# ETHERNET.net
KiCad netlist of a schematic drawn in Altium Designer
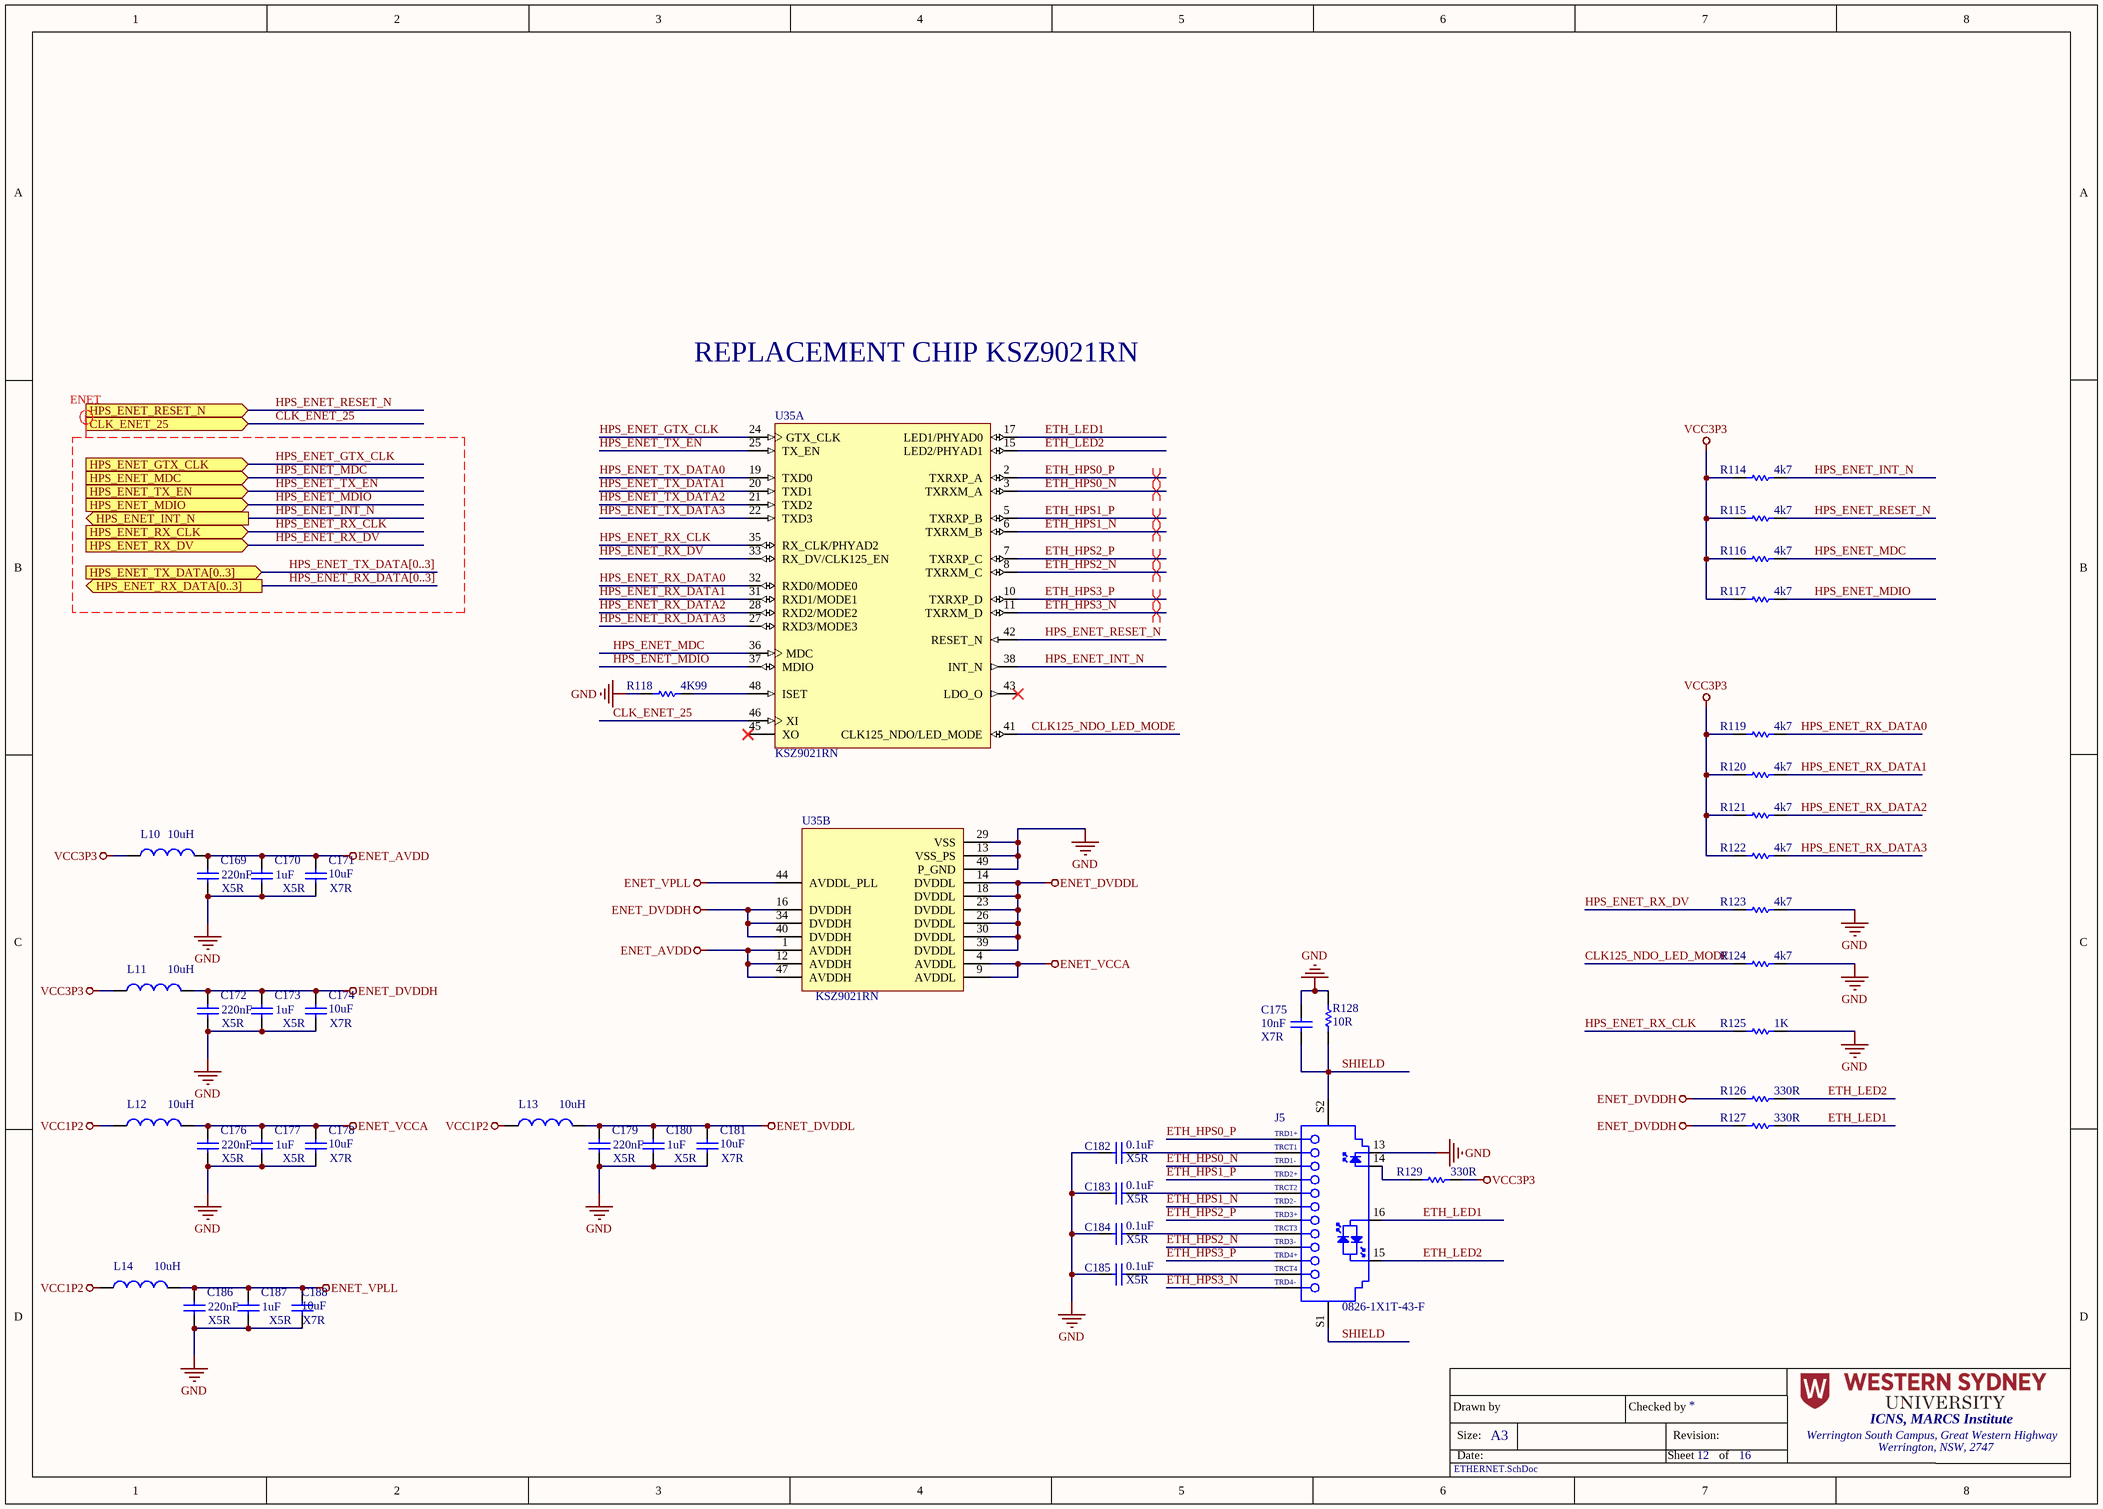
[diagram p0: ETHERNET.SchDoc]

(export (version "E")
  (design (tool "Eeschema 10.0.6"))
  (components
    (comp (ref "C169")
      (value "220nF")
      (footprint "CAP 0201 (0603)")
      (description "Cap Multilayer Ceramic 220nF 10V X5R 0201 ±10% Tolerance")
      (fields
        (field (name "TOLERANCE") "10%")
        (field (name "DIELECTRIC") "X5R")
        (field (name "MANUFACTURER PART NUMBER") "GRM033R61A224KE90D")
        (field (name "SOURCE") "ICNS_PropheseeLib.SchLib")
      )
      (libsource (lib "Western Sydney University - ICNS") (part "Symbol"))
    )
    (comp (ref "C170")
      (value "1uF")
      (footprint "CAP 0201 (0603)")
      (description "Cap Ceramic 1uF 10V X5R 10% Pad SMD 0201 85C T/R")
      (fields
        (field (name "TOLERANCE") "10%")
        (field (name "DIELECTRIC") "X5R")
        (field (name "MANUFACTURER") "Samsung")
        (field (name "SOURCE") "ICNS_PropheseeLib.SchLib")
      )
      (libsource (lib "Western Sydney University - ICNS") (part "Symbol"))
    )
    (comp (ref "C171")
      (value "10uF")
      (footprint "CAP 0805 (2012)")
      (description "0805 10 uF 10 V ±10 % Tolerance X7R Surface Mount Multilayer Ceramic Capacitor")
      (fields
        (field (name "TOLERANCE") "10%")
        (field (name "DIELECTRIC") "X7R")
        (field (name "MANUFACTURER PART NUMBER") "GCM21BR71A106KE22K")
        (field (name "SOURCE") "ICNS_PropheseeLib.SchLib")
      )
      (libsource (lib "Western Sydney University - ICNS") (part "GCM21BR71A106KE22K"))
    )
    (comp (ref "C172")
      (value "220nF")
      (footprint "CAP 0201 (0603)")
      (description "Cap Multilayer Ceramic 220nF 10V X5R 0201 ±10% Tolerance")
      (fields
        (field (name "TOLERANCE") "10%")
        (field (name "DIELECTRIC") "X5R")
        (field (name "MANUFACTURER PART NUMBER") "GRM033R61A224KE90D")
        (field (name "SOURCE") "ICNS_PropheseeLib.SchLib")
      )
      (libsource (lib "Western Sydney University - ICNS") (part "Symbol"))
    )
    (comp (ref "C173")
      (value "1uF")
      (footprint "CAP 0201 (0603)")
      (description "Cap Ceramic 1uF 10V X5R 10% Pad SMD 0201 85C T/R")
      (fields
        (field (name "TOLERANCE") "10%")
        (field (name "DIELECTRIC") "X5R")
        (field (name "MANUFACTURER") "Samsung")
        (field (name "SOURCE") "ICNS_PropheseeLib.SchLib")
      )
      (libsource (lib "Western Sydney University - ICNS") (part "Symbol"))
    )
    (comp (ref "C174")
      (value "10uF")
      (footprint "CAP 0805 (2012)")
      (description "0805 10 uF 10 V ±10 % Tolerance X7R Surface Mount Multilayer Ceramic Capacitor")
      (fields
        (field (name "TOLERANCE") "10%")
        (field (name "DIELECTRIC") "X7R")
        (field (name "MANUFACTURER PART NUMBER") "GCM21BR71A106KE22K")
        (field (name "SOURCE") "ICNS_PropheseeLib.SchLib")
      )
      (libsource (lib "Western Sydney University - ICNS") (part "GCM21BR71A106KE22K"))
    )
    (comp (ref "C175")
      (value "10nF")
      (footprint "CAP 0201 (0603)")
      (description "Cap Multilayer Ceramic 10nF 10V X7R 0201 ±10 % Tolerance SMT")
      (fields
        (field (name "TOLERANCE") "10%")
        (field (name "VOLTAGE") "10V")
        (field (name "DIELECTRIC") "X7R")
        (field (name "SOURCE") "ICNS_PropheseeLib.SchLib")
      )
      (libsource (lib "") (part "Symbol_3"))
    )
    (comp (ref "C176")
      (value "220nF")
      (footprint "CAP 0201 (0603)")
      (description "Cap Multilayer Ceramic 220nF 10V X5R 0201 ±10% Tolerance")
      (fields
        (field (name "TOLERANCE") "10%")
        (field (name "DIELECTRIC") "X5R")
        (field (name "MANUFACTURER PART NUMBER") "GRM033R61A224KE90D")
        (field (name "SOURCE") "ICNS_PropheseeLib.SchLib")
      )
      (libsource (lib "Western Sydney University - ICNS") (part "Symbol"))
    )
    (comp (ref "C177")
      (value "1uF")
      (footprint "CAP 0201 (0603)")
      (description "Cap Ceramic 1uF 10V X5R 10% Pad SMD 0201 85C T/R")
      (fields
        (field (name "TOLERANCE") "10%")
        (field (name "DIELECTRIC") "X5R")
        (field (name "MANUFACTURER") "Samsung")
        (field (name "SOURCE") "ICNS_PropheseeLib.SchLib")
      )
      (libsource (lib "Western Sydney University - ICNS") (part "Symbol"))
    )
    (comp (ref "C178")
      (value "10uF")
      (footprint "CAP 0805 (2012)")
      (description "0805 10 uF 10 V ±10 % Tolerance X7R Surface Mount Multilayer Ceramic Capacitor")
      (fields
        (field (name "TOLERANCE") "10%")
        (field (name "DIELECTRIC") "X7R")
        (field (name "MANUFACTURER PART NUMBER") "GCM21BR71A106KE22K")
        (field (name "SOURCE") "ICNS_PropheseeLib.SchLib")
      )
      (libsource (lib "Western Sydney University - ICNS") (part "GCM21BR71A106KE22K"))
    )
    (comp (ref "C179")
      (value "220nF")
      (footprint "CAP 0201 (0603)")
      (description "Cap Multilayer Ceramic 220nF 10V X5R 0201 ±10% Tolerance")
      (fields
        (field (name "TOLERANCE") "10%")
        (field (name "DIELECTRIC") "X5R")
        (field (name "MANUFACTURER PART NUMBER") "GRM033R61A224KE90D")
        (field (name "SOURCE") "ICNS_PropheseeLib.SchLib")
      )
      (libsource (lib "Western Sydney University - ICNS") (part "Symbol"))
    )
    (comp (ref "C180")
      (value "1uF")
      (footprint "CAP 0201 (0603)")
      (description "Cap Ceramic 1uF 10V X5R 10% Pad SMD 0201 85C T/R")
      (fields
        (field (name "TOLERANCE") "10%")
        (field (name "DIELECTRIC") "X5R")
        (field (name "MANUFACTURER") "Samsung")
        (field (name "SOURCE") "ICNS_PropheseeLib.SchLib")
      )
      (libsource (lib "Western Sydney University - ICNS") (part "Symbol"))
    )
    (comp (ref "C181")
      (value "10uF")
      (footprint "CAP 0805 (2012)")
      (description "0805 10 uF 10 V ±10 % Tolerance X7R Surface Mount Multilayer Ceramic Capacitor")
      (fields
        (field (name "TOLERANCE") "10%")
        (field (name "DIELECTRIC") "X7R")
        (field (name "MANUFACTURER PART NUMBER") "GCM21BR71A106KE22K")
        (field (name "SOURCE") "ICNS_PropheseeLib.SchLib")
      )
      (libsource (lib "Western Sydney University - ICNS") (part "GCM21BR71A106KE22K"))
    )
    (comp (ref "C182")
      (value "0.1uF")
      (footprint "CAP 0201 (0603)")
      (description "Cap Ceramic 0.1uF 10V X5R 10% Pad SMD 0201 85C T/R")
      (fields
        (field (name "TOLERANCE") "10%")
        (field (name "DIELECTRIC") "X5R")
        (field (name "MANUFACTURER PART NUMBER") "CL03A104KP3NNNC")
        (field (name "SOURCE") "ICNS_PropheseeLib.SchLib")
      )
      (libsource (lib "Western Sydney University - ICNS") (part "CL03A104KP3NNNC"))
    )
    (comp (ref "C183")
      (value "0.1uF")
      (footprint "CAP 0201 (0603)")
      (description "Cap Ceramic 0.1uF 10V X5R 10% Pad SMD 0201 85C T/R")
      (fields
        (field (name "TOLERANCE") "10%")
        (field (name "DIELECTRIC") "X5R")
        (field (name "MANUFACTURER PART NUMBER") "CL03A104KP3NNNC")
        (field (name "SOURCE") "ICNS_PropheseeLib.SchLib")
      )
      (libsource (lib "Western Sydney University - ICNS") (part "CL03A104KP3NNNC"))
    )
    (comp (ref "C184")
      (value "0.1uF")
      (footprint "CAP 0201 (0603)")
      (description "Cap Ceramic 0.1uF 10V X5R 10% Pad SMD 0201 85C T/R")
      (fields
        (field (name "TOLERANCE") "10%")
        (field (name "DIELECTRIC") "X5R")
        (field (name "MANUFACTURER PART NUMBER") "CL03A104KP3NNNC")
        (field (name "SOURCE") "ICNS_PropheseeLib.SchLib")
      )
      (libsource (lib "Western Sydney University - ICNS") (part "CL03A104KP3NNNC"))
    )
    (comp (ref "C185")
      (value "0.1uF")
      (footprint "CAP 0201 (0603)")
      (description "Cap Ceramic 0.1uF 10V X5R 10% Pad SMD 0201 85C T/R")
      (fields
        (field (name "TOLERANCE") "10%")
        (field (name "DIELECTRIC") "X5R")
        (field (name "MANUFACTURER PART NUMBER") "CL03A104KP3NNNC")
        (field (name "SOURCE") "ICNS_PropheseeLib.SchLib")
      )
      (libsource (lib "Western Sydney University - ICNS") (part "CL03A104KP3NNNC"))
    )
    (comp (ref "C186")
      (value "220nF")
      (footprint "CAP 0201 (0603)")
      (description "Cap Multilayer Ceramic 220nF 10V X5R 0201 ±10% Tolerance")
      (fields
        (field (name "TOLERANCE") "10%")
        (field (name "DIELECTRIC") "X5R")
        (field (name "MANUFACTURER PART NUMBER") "GRM033R61A224KE90D")
        (field (name "SOURCE") "ICNS_PropheseeLib.SchLib")
      )
      (libsource (lib "Western Sydney University - ICNS") (part "Symbol"))
    )
    (comp (ref "C187")
      (value "1uF")
      (footprint "CAP 0201 (0603)")
      (description "Cap Ceramic 1uF 10V X5R 10% Pad SMD 0201 85C T/R")
      (fields
        (field (name "TOLERANCE") "10%")
        (field (name "DIELECTRIC") "X5R")
        (field (name "MANUFACTURER") "Samsung")
        (field (name "SOURCE") "ICNS_PropheseeLib.SchLib")
      )
      (libsource (lib "Western Sydney University - ICNS") (part "Symbol"))
    )
    (comp (ref "C188")
      (value "10uF")
      (footprint "CAP 0805 (2012)")
      (description "0805 10 uF 10 V ±10 % Tolerance X7R Surface Mount Multilayer Ceramic Capacitor")
      (fields
        (field (name "TOLERANCE") "10%")
        (field (name "DIELECTRIC") "X7R")
        (field (name "MANUFACTURER PART NUMBER") "GCM21BR71A106KE22K")
        (field (name "SOURCE") "ICNS_PropheseeLib.SchLib")
      )
      (libsource (lib "Western Sydney University - ICNS") (part "GCM21BR71A106KE22K"))
    )
    (comp (ref "J5")
      (value "0826-1X1T-43-F")
      (footprint "BEL_0826-1X1T-43-F")
      (description "Conn Modular Jack RCP 12 POS 2.03mm Solder RA Thru-Hole 16 Terminal 1 Port Tray")
      (fields (field (name "MANUFACTURER") "Bel") (field (name "SOURCE") "ICNS_PropheseeLib.SchLib"))
      (libsource (lib "Western Sydney University - ICNS") (part "0826-1X1T-43-F"))
    )
    (comp (ref "L10")
      (value "10uH")
      (footprint "INDC2012X15N")
      (description "Inductor WE-PMI Series 10 µH; Multilayer SMD ; 0805 Case; 25MHz Q: 35 650mA 500mO")
      (fields
        (field (name "MANUFACTURER") "Wurth Electronics")
        (field (name "MANUFACTURER PART NUMBER") "74479777310")
        (field (name "SOURCE") "ICNS_PropheseeLib.SchLib")
      )
      (libsource (lib "") (part "Symbol_2"))
    )
    (comp (ref "L11")
      (value "10uH")
      (footprint "INDC2012X15N")
      (description "Inductor WE-PMI Series 10 µH; Multilayer SMD ; 0805 Case; 25MHz Q: 35 650mA 500mO")
      (fields
        (field (name "MANUFACTURER") "Wurth Electronics")
        (field (name "MANUFACTURER PART NUMBER") "74479777310")
        (field (name "SOURCE") "ICNS_PropheseeLib.SchLib")
      )
      (libsource (lib "") (part "Symbol_2"))
    )
    (comp (ref "L12")
      (value "10uH")
      (footprint "INDC2012X15N")
      (description "Inductor WE-PMI Series 10 µH; Multilayer SMD ; 0805 Case; 25MHz Q: 35 650mA 500mO")
      (fields
        (field (name "MANUFACTURER") "Wurth Electronics")
        (field (name "MANUFACTURER PART NUMBER") "74479777310")
        (field (name "SOURCE") "ICNS_PropheseeLib.SchLib")
      )
      (libsource (lib "") (part "Symbol_2"))
    )
    (comp (ref "L13")
      (value "10uH")
      (footprint "INDC2012X15N")
      (description "Inductor WE-PMI Series 10 µH; Multilayer SMD ; 0805 Case; 25MHz Q: 35 650mA 500mO")
      (fields
        (field (name "MANUFACTURER") "Wurth Electronics")
        (field (name "MANUFACTURER PART NUMBER") "74479777310")
        (field (name "SOURCE") "ICNS_PropheseeLib.SchLib")
      )
      (libsource (lib "") (part "Symbol_2"))
    )
    (comp (ref "L14")
      (value "10uH")
      (footprint "INDC2012X15N")
      (description "Inductor WE-PMI Series 10 µH; Multilayer SMD ; 0805 Case; 25MHz Q: 35 650mA 500mO")
      (fields
        (field (name "MANUFACTURER") "Wurth Electronics")
        (field (name "MANUFACTURER PART NUMBER") "74479777310")
        (field (name "SOURCE") "ICNS_PropheseeLib.SchLib")
      )
      (libsource (lib "") (part "Symbol_2"))
    )
    (comp (ref "R114")
      (value "4k7")
      (footprint "RES 0201 (0603)")
      (description "Res Thick Film 0201 4.7K Ohm 1% 1/20W ±200ppm/°C Molded SMD Paper T/R")
      (fields
        (field (name "TOLERANCE") "1%")
        (field (name "MANUFACTURER") "Yageo")
        (field (name "SOURCE") "ICNS_PropheseeLib.SchLib")
      )
      (libsource (lib "") (part "Symbol_1"))
    )
    (comp (ref "R115")
      (value "4k7")
      (footprint "RES 0201 (0603)")
      (description "Res Thick Film 0201 4.7K Ohm 1% 1/20W ±200ppm/°C Molded SMD Paper T/R")
      (fields
        (field (name "TOLERANCE") "1%")
        (field (name "MANUFACTURER") "Yageo")
        (field (name "SOURCE") "ICNS_PropheseeLib.SchLib")
      )
      (libsource (lib "") (part "Symbol_1"))
    )
    (comp (ref "R116")
      (value "4k7")
      (footprint "RES 0201 (0603)")
      (description "Res Thick Film 0201 4.7K Ohm 1% 1/20W ±200ppm/°C Molded SMD Paper T/R")
      (fields
        (field (name "TOLERANCE") "1%")
        (field (name "MANUFACTURER") "Yageo")
        (field (name "SOURCE") "ICNS_PropheseeLib.SchLib")
      )
      (libsource (lib "") (part "Symbol_1"))
    )
    (comp (ref "R117")
      (value "4k7")
      (footprint "RES 0201 (0603)")
      (description "Res Thick Film 0201 4.7K Ohm 1% 1/20W ±200ppm/°C Molded SMD Paper T/R")
      (fields
        (field (name "TOLERANCE") "1%")
        (field (name "MANUFACTURER") "Yageo")
        (field (name "SOURCE") "ICNS_PropheseeLib.SchLib")
      )
      (libsource (lib "") (part "Symbol_1"))
    )
    (comp (ref "R118")
      (value "4K99")
      (footprint "RES 0201 (0603)")
      (description "Res Thick Film 0201 4.99K Ohm 1% 1/20W ±100ppm/°C Molded SMD SMD Paper T/R")
      (fields
        (field (name "TOLERANCE") "1%")
        (field (name "MANUFACTURER") "Vishay Dale")
        (field (name "SOURCE") "ICNS_PropheseeLib.SchLib")
      )
      (libsource (lib "") (part "Symbol_1"))
    )
    (comp (ref "R119")
      (value "4k7")
      (footprint "RES 0201 (0603)")
      (description "Res Thick Film 0201 4.7K Ohm 1% 1/20W ±200ppm/°C Molded SMD Paper T/R")
      (fields
        (field (name "TOLERANCE") "1%")
        (field (name "MANUFACTURER") "Yageo")
        (field (name "SOURCE") "ICNS_PropheseeLib.SchLib")
      )
      (libsource (lib "") (part "Symbol_1"))
    )
    (comp (ref "R120")
      (value "4k7")
      (footprint "RES 0201 (0603)")
      (description "Res Thick Film 0201 4.7K Ohm 1% 1/20W ±200ppm/°C Molded SMD Paper T/R")
      (fields
        (field (name "TOLERANCE") "1%")
        (field (name "MANUFACTURER") "Yageo")
        (field (name "SOURCE") "ICNS_PropheseeLib.SchLib")
      )
      (libsource (lib "") (part "Symbol_1"))
    )
    (comp (ref "R121")
      (value "4k7")
      (footprint "RES 0201 (0603)")
      (description "Res Thick Film 0201 4.7K Ohm 1% 1/20W ±200ppm/°C Molded SMD Paper T/R")
      (fields
        (field (name "TOLERANCE") "1%")
        (field (name "MANUFACTURER") "Yageo")
        (field (name "SOURCE") "ICNS_PropheseeLib.SchLib")
      )
      (libsource (lib "") (part "Symbol_1"))
    )
    (comp (ref "R122")
      (value "4k7")
      (footprint "RES 0201 (0603)")
      (description "Res Thick Film 0201 4.7K Ohm 1% 1/20W ±200ppm/°C Molded SMD Paper T/R")
      (fields
        (field (name "TOLERANCE") "1%")
        (field (name "MANUFACTURER") "Yageo")
        (field (name "SOURCE") "ICNS_PropheseeLib.SchLib")
      )
      (libsource (lib "") (part "Symbol_1"))
    )
    (comp (ref "R123")
      (value "4k7")
      (footprint "RES 0201 (0603)")
      (description "Res Thick Film 0201 4.7K Ohm 1% 1/20W ±200ppm/°C Molded SMD Paper T/R")
      (fields
        (field (name "TOLERANCE") "1%")
        (field (name "MANUFACTURER") "Yageo")
        (field (name "SOURCE") "ICNS_PropheseeLib.SchLib")
      )
      (libsource (lib "") (part "Symbol_1"))
    )
    (comp (ref "R124")
      (value "4k7")
      (footprint "RES 0201 (0603)")
      (description "Res Thick Film 0201 4.7K Ohm 1% 1/20W ±200ppm/°C Molded SMD Paper T/R")
      (fields
        (field (name "TOLERANCE") "1%")
        (field (name "MANUFACTURER") "Yageo")
        (field (name "SOURCE") "ICNS_PropheseeLib.SchLib")
      )
      (libsource (lib "") (part "Symbol_1"))
    )
    (comp (ref "R125")
      (value "1K")
      (footprint "RES 0201 (0603)")
      (description "Res Thick Film 0201 1K Ohm 1% 0.05W(1/20W) ±200ppm/C Pad SMD Automotive T/R")
      (fields
        (field (name "TOLERANCE") "1%")
        (field (name "MANUFACTURER") "Yageo")
        (field (name "SOURCE") "ICNS_PropheseeLib.SchLib")
      )
      (libsource (lib "") (part "Symbol_1"))
    )
    (comp (ref "R126")
      (value "330R")
      (footprint "RES 0402 (1005)")
      (description "Res Thick Film 0402 330 Ohm 1% 0.2W ±100ppm/°C Molded SMD SMD Paper T/R")
      (fields
        (field (name "TOLERANCE") "1%")
        (field (name "Comment") "CRCW0402330RFKEDHP")
        (field (name "SOURCE") "ICNS_PropheseeLib.SchLib")
      )
      (libsource (lib "") (part "Symbol_1"))
    )
    (comp (ref "R127")
      (value "330R")
      (footprint "RES 0402 (1005)")
      (description "Res Thick Film 0402 330 Ohm 1% 0.2W ±100ppm/°C Molded SMD SMD Paper T/R")
      (fields
        (field (name "TOLERANCE") "1%")
        (field (name "Comment") "CRCW0402330RFKEDHP")
        (field (name "SOURCE") "ICNS_PropheseeLib.SchLib")
      )
      (libsource (lib "") (part "Symbol_1"))
    )
    (comp (ref "R128")
      (value "10R")
      (footprint "RES 0402 (1005)")
      (description "Res Thick Film 0402 10 Ohm 1% 0.125W(1/8W) ±100ppm/C Pad SMD T/R")
      (fields
        (field (name "TOLERANCE") "1%")
        (field (name "MANUFACTURER") "TE Connectivity")
        (field (name "SOURCE") "ICNS_PropheseeLib.SchLib")
      )
      (libsource (lib "Western Sydney University - ICNS") (part "CRGP0402F10R"))
    )
    (comp (ref "R129")
      (value "330R")
      (footprint "RES 0402 (1005)")
      (description "Res Thick Film 0402 330 Ohm 1% 0.2W ±100ppm/°C Molded SMD SMD Paper T/R")
      (fields
        (field (name "TOLERANCE") "1%")
        (field (name "Comment") "CRCW0402330RFKEDHP")
        (field (name "SOURCE") "ICNS_PropheseeLib.SchLib")
      )
      (libsource (lib "") (part "Symbol_1"))
    )
    (comp (ref "U35")
      (value "KSZ9021RN")
      (footprint "MICL-VQFN-48-5100x5100TP_V")
      (description "Ethernet TXRX Single Chip 1-Port 1.2V 10Mbps/100Mbps/1000Mbps 48-Pin QFN EP")
      (fields (field (name "MANUFACTURER") "Microchip") (field (name "SOURCE") "ICNS_PropheseeLib.SchLib"))
      (libsource (lib "Western Sydney University - ICNS") (part "KSZ9021RN"))
    )
  )
  (nets
    (net (code "1") (name "/CLK125_NDO_LED_MODE") (class "Default")
      (node (ref "R124") (pin "1") (pinfunction "1_1") (pintype "passive"))
      (node (ref "U35") (pin "41") (pinfunction "CLK125_NDO/LED_MODE_41") (pintype "bidirectional"))
    )
    (net (code "2") (name "/CLK_ENET_25") (class "Default")
      (node (ref "U35") (pin "46") (pinfunction "XI_46") (pintype "input"))
    )
    (net (code "3") (name "/ETH_HPS0_N") (class "Default")
      (node (ref "J5") (pin "10") (pinfunction "TRD1-_10") (pintype "passive"))
      (node (ref "U35") (pin "3") (pinfunction "TXRXM_A_3") (pintype "bidirectional"))
    )
    (net (code "4") (name "/ETH_HPS0_P") (class "Default")
      (node (ref "J5") (pin "11") (pinfunction "TRD1+_11") (pintype "passive"))
      (node (ref "U35") (pin "2") (pinfunction "TXRXP_A_2") (pintype "bidirectional"))
    )
    (net (code "5") (name "/ETH_HPS1_N") (class "Default")
      (node (ref "J5") (pin "5") (pinfunction "TRD2-_5") (pintype "passive"))
      (node (ref "U35") (pin "6") (pinfunction "TXRXM_B_6") (pintype "bidirectional"))
    )
    (net (code "6") (name "/ETH_HPS1_P") (class "Default")
      (node (ref "J5") (pin "4") (pinfunction "TRD2+_4") (pintype "passive"))
      (node (ref "U35") (pin "5") (pinfunction "TXRXP_B_5") (pintype "bidirectional"))
    )
    (net (code "7") (name "/ETH_HPS2_N") (class "Default")
      (node (ref "J5") (pin "2") (pinfunction "TRD3-_2") (pintype "passive"))
      (node (ref "U35") (pin "8") (pinfunction "TXRXM_C_8") (pintype "bidirectional"))
    )
    (net (code "8") (name "/ETH_HPS2_P") (class "Default")
      (node (ref "J5") (pin "3") (pinfunction "TRD3+_3") (pintype "passive"))
      (node (ref "U35") (pin "7") (pinfunction "TXRXP_C_7") (pintype "bidirectional"))
    )
    (net (code "9") (name "/ETH_HPS3_N") (class "Default")
      (node (ref "J5") (pin "9") (pinfunction "TRD4-_9") (pintype "passive"))
      (node (ref "U35") (pin "11") (pinfunction "TXRXM_D_11") (pintype "bidirectional"))
    )
    (net (code "10") (name "/ETH_HPS3_P") (class "Default")
      (node (ref "J5") (pin "8") (pinfunction "TRD4+_8") (pintype "passive"))
      (node (ref "U35") (pin "10") (pinfunction "TXRXP_D_10") (pintype "bidirectional"))
    )
    (net (code "11") (name "/ETH_LED1") (class "Default")
      (node (ref "J5") (pin "16") (pinfunction "16_16") (pintype "passive"))
      (node (ref "R127") (pin "1") (pinfunction "1_1") (pintype "passive"))
      (node (ref "U35") (pin "17") (pinfunction "LED1/PHYAD0_17") (pintype "bidirectional"))
    )
    (net (code "12") (name "/ETH_LED2") (class "Default")
      (node (ref "J5") (pin "15") (pinfunction "15_15") (pintype "passive"))
      (node (ref "R126") (pin "1") (pinfunction "1_1") (pintype "passive"))
      (node (ref "U35") (pin "15") (pinfunction "LED2/PHYAD1_15") (pintype "bidirectional"))
    )
    (net (code "13") (name "/HPS_ENET_GTX_CLK") (class "Default")
      (node (ref "U35") (pin "24") (pinfunction "GTX_CLK_24") (pintype "input"))
    )
    (net (code "14") (name "/HPS_ENET_INT_N") (class "Default")
      (node (ref "R114") (pin "2") (pinfunction "2_2") (pintype "passive"))
      (node (ref "U35") (pin "38") (pinfunction "INT_N_38") (pintype "output"))
    )
    (net (code "15") (name "/HPS_ENET_MDC") (class "Default")
      (node (ref "R116") (pin "2") (pinfunction "2_2") (pintype "passive"))
      (node (ref "U35") (pin "36") (pinfunction "MDC_36") (pintype "input"))
    )
    (net (code "16") (name "/HPS_ENET_MDIO") (class "Default")
      (node (ref "R117") (pin "2") (pinfunction "2_2") (pintype "passive"))
      (node (ref "U35") (pin "37") (pinfunction "MDIO_37") (pintype "bidirectional"))
    )
    (net (code "17") (name "/HPS_ENET_RESET_N") (class "Default")
      (node (ref "R115") (pin "2") (pinfunction "2_2") (pintype "passive"))
      (node (ref "U35") (pin "42") (pinfunction "RESET_N_42") (pintype "input"))
    )
    (net (code "18") (name "/HPS_ENET_RX_CLK") (class "Default")
      (node (ref "R125") (pin "1") (pinfunction "1_1") (pintype "passive"))
      (node (ref "U35") (pin "35") (pinfunction "RX_CLK/PHYAD2_35") (pintype "bidirectional"))
    )
    (net (code "19") (name "/HPS_ENET_RX_DATA0") (class "Default")
      (node (ref "R119") (pin "2") (pinfunction "2_2") (pintype "passive"))
      (node (ref "U35") (pin "32") (pinfunction "RXD0/MODE0_32") (pintype "bidirectional"))
    )
    (net (code "20") (name "/HPS_ENET_RX_DATA1") (class "Default")
      (node (ref "R120") (pin "2") (pinfunction "2_2") (pintype "passive"))
      (node (ref "U35") (pin "31") (pinfunction "RXD1/MODE1_31") (pintype "bidirectional"))
    )
    (net (code "21") (name "/HPS_ENET_RX_DATA2") (class "Default")
      (node (ref "R121") (pin "2") (pinfunction "2_2") (pintype "passive"))
      (node (ref "U35") (pin "28") (pinfunction "RXD2/MODE2_28") (pintype "bidirectional"))
    )
    (net (code "22") (name "/HPS_ENET_RX_DATA3") (class "Default")
      (node (ref "R122") (pin "2") (pinfunction "2_2") (pintype "passive"))
      (node (ref "U35") (pin "27") (pinfunction "RXD3/MODE3_27") (pintype "bidirectional"))
    )
    (net (code "24") (name "/HPS_ENET_RX_DV") (class "Default")
      (node (ref "R123") (pin "1") (pinfunction "1_1") (pintype "passive"))
      (node (ref "U35") (pin "33") (pinfunction "RX_DV/CLK125_EN_33") (pintype "bidirectional"))
    )
    (net (code "25") (name "/HPS_ENET_TX_DATA0") (class "Default")
      (node (ref "U35") (pin "19") (pinfunction "TXD0_19") (pintype "input"))
    )
    (net (code "26") (name "/HPS_ENET_TX_DATA1") (class "Default")
      (node (ref "U35") (pin "20") (pinfunction "TXD1_20") (pintype "input"))
    )
    (net (code "27") (name "/HPS_ENET_TX_DATA2") (class "Default")
      (node (ref "U35") (pin "21") (pinfunction "TXD2_21") (pintype "input"))
    )
    (net (code "28") (name "/HPS_ENET_TX_DATA3") (class "Default")
      (node (ref "U35") (pin "22") (pinfunction "TXD3_22") (pintype "input"))
    )
    (net (code "30") (name "/HPS_ENET_TX_EN") (class "Default")
      (node (ref "U35") (pin "25") (pinfunction "TX_EN_25") (pintype "input"))
    )
    (net (code "31") (name "/SHIELD") (class "Default")
      (node (ref "C175") (pin "2") (pinfunction "2_2") (pintype "passive"))
      (node (ref "J5") (pin "S1") (pinfunction "S1_S1") (pintype "passive"))
      (node (ref "J5") (pin "S2") (pinfunction "S2_S2") (pintype "passive"))
      (node (ref "R128") (pin "2") (pinfunction "2_2") (pintype "passive"))
    )
    (net (code "32") (name "ENET_AVDD") (class "Default")
      (node (ref "C169") (pin "1") (pinfunction "1_1") (pintype "passive"))
      (node (ref "C170") (pin "1") (pinfunction "1_1") (pintype "passive"))
      (node (ref "C171") (pin "1") (pinfunction "1_1") (pintype "passive"))
      (node (ref "L10") (pin "2") (pinfunction "2_2") (pintype "passive"))
      (node (ref "U35") (pin "1") (pinfunction "AVDDH_1") (pintype "power_in"))
      (node (ref "U35") (pin "12") (pinfunction "AVDDH_12") (pintype "power_in"))
      (node (ref "U35") (pin "47") (pinfunction "AVDDH_47") (pintype "power_in"))
    )
    (net (code "33") (name "ENET_DVDDH") (class "Default")
      (node (ref "C172") (pin "1") (pinfunction "1_1") (pintype "passive"))
      (node (ref "C173") (pin "1") (pinfunction "1_1") (pintype "passive"))
      (node (ref "C174") (pin "1") (pinfunction "1_1") (pintype "passive"))
      (node (ref "L11") (pin "2") (pinfunction "2_2") (pintype "passive"))
      (node (ref "R126") (pin "2") (pinfunction "2_2") (pintype "passive"))
      (node (ref "R127") (pin "2") (pinfunction "2_2") (pintype "passive"))
      (node (ref "U35") (pin "16") (pinfunction "DVDDH_16") (pintype "power_in"))
      (node (ref "U35") (pin "34") (pinfunction "DVDDH_34") (pintype "power_in"))
      (node (ref "U35") (pin "40") (pinfunction "DVDDH_40") (pintype "power_in"))
    )
    (net (code "34") (name "ENET_DVDDL") (class "Default")
      (node (ref "C179") (pin "1") (pinfunction "1_1") (pintype "passive"))
      (node (ref "C180") (pin "1") (pinfunction "1_1") (pintype "passive"))
      (node (ref "C181") (pin "1") (pinfunction "1_1") (pintype "passive"))
      (node (ref "L13") (pin "2") (pinfunction "2_2") (pintype "passive"))
      (node (ref "U35") (pin "14") (pinfunction "DVDDL_14") (pintype "power_in"))
      (node (ref "U35") (pin "18") (pinfunction "DVDDL_18") (pintype "power_in"))
      (node (ref "U35") (pin "23") (pinfunction "DVDDL_23") (pintype "power_in"))
      (node (ref "U35") (pin "26") (pinfunction "DVDDL_26") (pintype "power_in"))
      (node (ref "U35") (pin "30") (pinfunction "DVDDL_30") (pintype "power_in"))
      (node (ref "U35") (pin "39") (pinfunction "DVDDL_39") (pintype "power_in"))
    )
    (net (code "35") (name "ENET_VCCA") (class "Default")
      (node (ref "C176") (pin "1") (pinfunction "1_1") (pintype "passive"))
      (node (ref "C177") (pin "1") (pinfunction "1_1") (pintype "passive"))
      (node (ref "C178") (pin "1") (pinfunction "1_1") (pintype "passive"))
      (node (ref "L12") (pin "2") (pinfunction "2_2") (pintype "passive"))
      (node (ref "U35") (pin "4") (pinfunction "AVDDL_4") (pintype "power_in"))
      (node (ref "U35") (pin "9") (pinfunction "AVDDL_9") (pintype "power_in"))
    )
    (net (code "36") (name "ENET_VPLL") (class "Default")
      (node (ref "C186") (pin "1") (pinfunction "1_1") (pintype "passive"))
      (node (ref "C187") (pin "1") (pinfunction "1_1") (pintype "passive"))
      (node (ref "C188") (pin "1") (pinfunction "1_1") (pintype "passive"))
      (node (ref "L14") (pin "2") (pinfunction "2_2") (pintype "passive"))
      (node (ref "U35") (pin "44") (pinfunction "AVDDL_PLL_44") (pintype "power_in"))
    )
    (net (code "37") (name "GND") (class "Default")
      (node (ref "C169") (pin "2") (pinfunction "2_2") (pintype "passive"))
      (node (ref "C170") (pin "2") (pinfunction "2_2") (pintype "passive"))
      (node (ref "C171") (pin "2") (pinfunction "2_2") (pintype "passive"))
      (node (ref "C172") (pin "2") (pinfunction "2_2") (pintype "passive"))
      (node (ref "C173") (pin "2") (pinfunction "2_2") (pintype "passive"))
      (node (ref "C174") (pin "2") (pinfunction "2_2") (pintype "passive"))
      (node (ref "C175") (pin "1") (pinfunction "1_1") (pintype "passive"))
      (node (ref "C176") (pin "2") (pinfunction "2_2") (pintype "passive"))
      (node (ref "C177") (pin "2") (pinfunction "2_2") (pintype "passive"))
      (node (ref "C178") (pin "2") (pinfunction "2_2") (pintype "passive"))
      (node (ref "C179") (pin "2") (pinfunction "2_2") (pintype "passive"))
      (node (ref "C180") (pin "2") (pinfunction "2_2") (pintype "passive"))
      (node (ref "C181") (pin "2") (pinfunction "2_2") (pintype "passive"))
      (node (ref "C182") (pin "1") (pinfunction "1_1") (pintype "passive"))
      (node (ref "C183") (pin "1") (pinfunction "1_1") (pintype "passive"))
      (node (ref "C184") (pin "1") (pinfunction "1_1") (pintype "passive"))
      (node (ref "C185") (pin "1") (pinfunction "1_1") (pintype "passive"))
      (node (ref "C186") (pin "2") (pinfunction "2_2") (pintype "passive"))
      (node (ref "C187") (pin "2") (pinfunction "2_2") (pintype "passive"))
      (node (ref "C188") (pin "2") (pinfunction "2_2") (pintype "passive"))
      (node (ref "J5") (pin "13") (pinfunction "13_13") (pintype "passive"))
      (node (ref "R118") (pin "2") (pinfunction "2_2") (pintype "passive"))
      (node (ref "R123") (pin "2") (pinfunction "2_2") (pintype "passive"))
      (node (ref "R124") (pin "2") (pinfunction "2_2") (pintype "passive"))
      (node (ref "R125") (pin "2") (pinfunction "2_2") (pintype "passive"))
      (node (ref "R128") (pin "1") (pinfunction "1_1") (pintype "passive"))
      (node (ref "U35") (pin "13") (pinfunction "VSS_PS_13") (pintype "power_in"))
      (node (ref "U35") (pin "29") (pinfunction "VSS_29") (pintype "power_in"))
      (node (ref "U35") (pin "49") (pinfunction "P_GND_49") (pintype "power_in"))
    )
    (net (code "38") (name "Net-(J5-Pad14)") (class "Default")
      (node (ref "J5") (pin "14") (pinfunction "14_14") (pintype "passive"))
      (node (ref "R129") (pin "2") (pinfunction "2_2") (pintype "passive"))
    )
    (net (code "39") (name "Net-(J5-TRCT1)") (class "Default")
      (node (ref "C182") (pin "2") (pinfunction "2_2") (pintype "passive"))
      (node (ref "J5") (pin "12") (pinfunction "TRCT1_12") (pintype "passive"))
    )
    (net (code "40") (name "Net-(J5-TRCT2)") (class "Default")
      (node (ref "C183") (pin "2") (pinfunction "2_2") (pintype "passive"))
      (node (ref "J5") (pin "6") (pinfunction "TRCT2_6") (pintype "passive"))
    )
    (net (code "41") (name "Net-(J5-TRCT3)") (class "Default")
      (node (ref "C184") (pin "2") (pinfunction "2_2") (pintype "passive"))
      (node (ref "J5") (pin "1") (pinfunction "TRCT3_1") (pintype "passive"))
    )
    (net (code "42") (name "Net-(J5-TRCT4)") (class "Default")
      (node (ref "C185") (pin "2") (pinfunction "2_2") (pintype "passive"))
      (node (ref "J5") (pin "7") (pinfunction "TRCT4_7") (pintype "passive"))
    )
    (net (code "43") (name "Net-(U35A-ISET)") (class "Default")
      (node (ref "R118") (pin "1") (pinfunction "1_1") (pintype "passive"))
      (node (ref "U35") (pin "48") (pinfunction "ISET_48") (pintype "input"))
    )
    (net (code "44") (name "VCC1P2") (class "Default")
      (node (ref "L12") (pin "1") (pinfunction "1_1") (pintype "passive"))
      (node (ref "L13") (pin "1") (pinfunction "1_1") (pintype "passive"))
      (node (ref "L14") (pin "1") (pinfunction "1_1") (pintype "passive"))
    )
    (net (code "45") (name "VCC3P3") (class "Default")
      (node (ref "L10") (pin "1") (pinfunction "1_1") (pintype "passive"))
      (node (ref "L11") (pin "1") (pinfunction "1_1") (pintype "passive"))
      (node (ref "R114") (pin "1") (pinfunction "1_1") (pintype "passive"))
      (node (ref "R115") (pin "1") (pinfunction "1_1") (pintype "passive"))
      (node (ref "R116") (pin "1") (pinfunction "1_1") (pintype "passive"))
      (node (ref "R117") (pin "1") (pinfunction "1_1") (pintype "passive"))
      (node (ref "R119") (pin "1") (pinfunction "1_1") (pintype "passive"))
      (node (ref "R120") (pin "1") (pinfunction "1_1") (pintype "passive"))
      (node (ref "R121") (pin "1") (pinfunction "1_1") (pintype "passive"))
      (node (ref "R122") (pin "1") (pinfunction "1_1") (pintype "passive"))
      (node (ref "R129") (pin "1") (pinfunction "1_1") (pintype "passive"))
    )
    (net (code "46") (name "unconnected-(U35A-LDO_O-Pad43)") (class "Default")
      (node (ref "U35") (pin "43") (pinfunction "LDO_O_43") (pintype "output+no_connect"))
    )
    (net (code "47") (name "unconnected-(U35A-XO-Pad45)") (class "Default")
      (node (ref "U35") (pin "45") (pinfunction "XO_45") (pintype "passive+no_connect"))
    )
  )
)
